# Cube_8x8x8_LED_Base.net
KiCad netlist of a schematic drawn in EAGLE
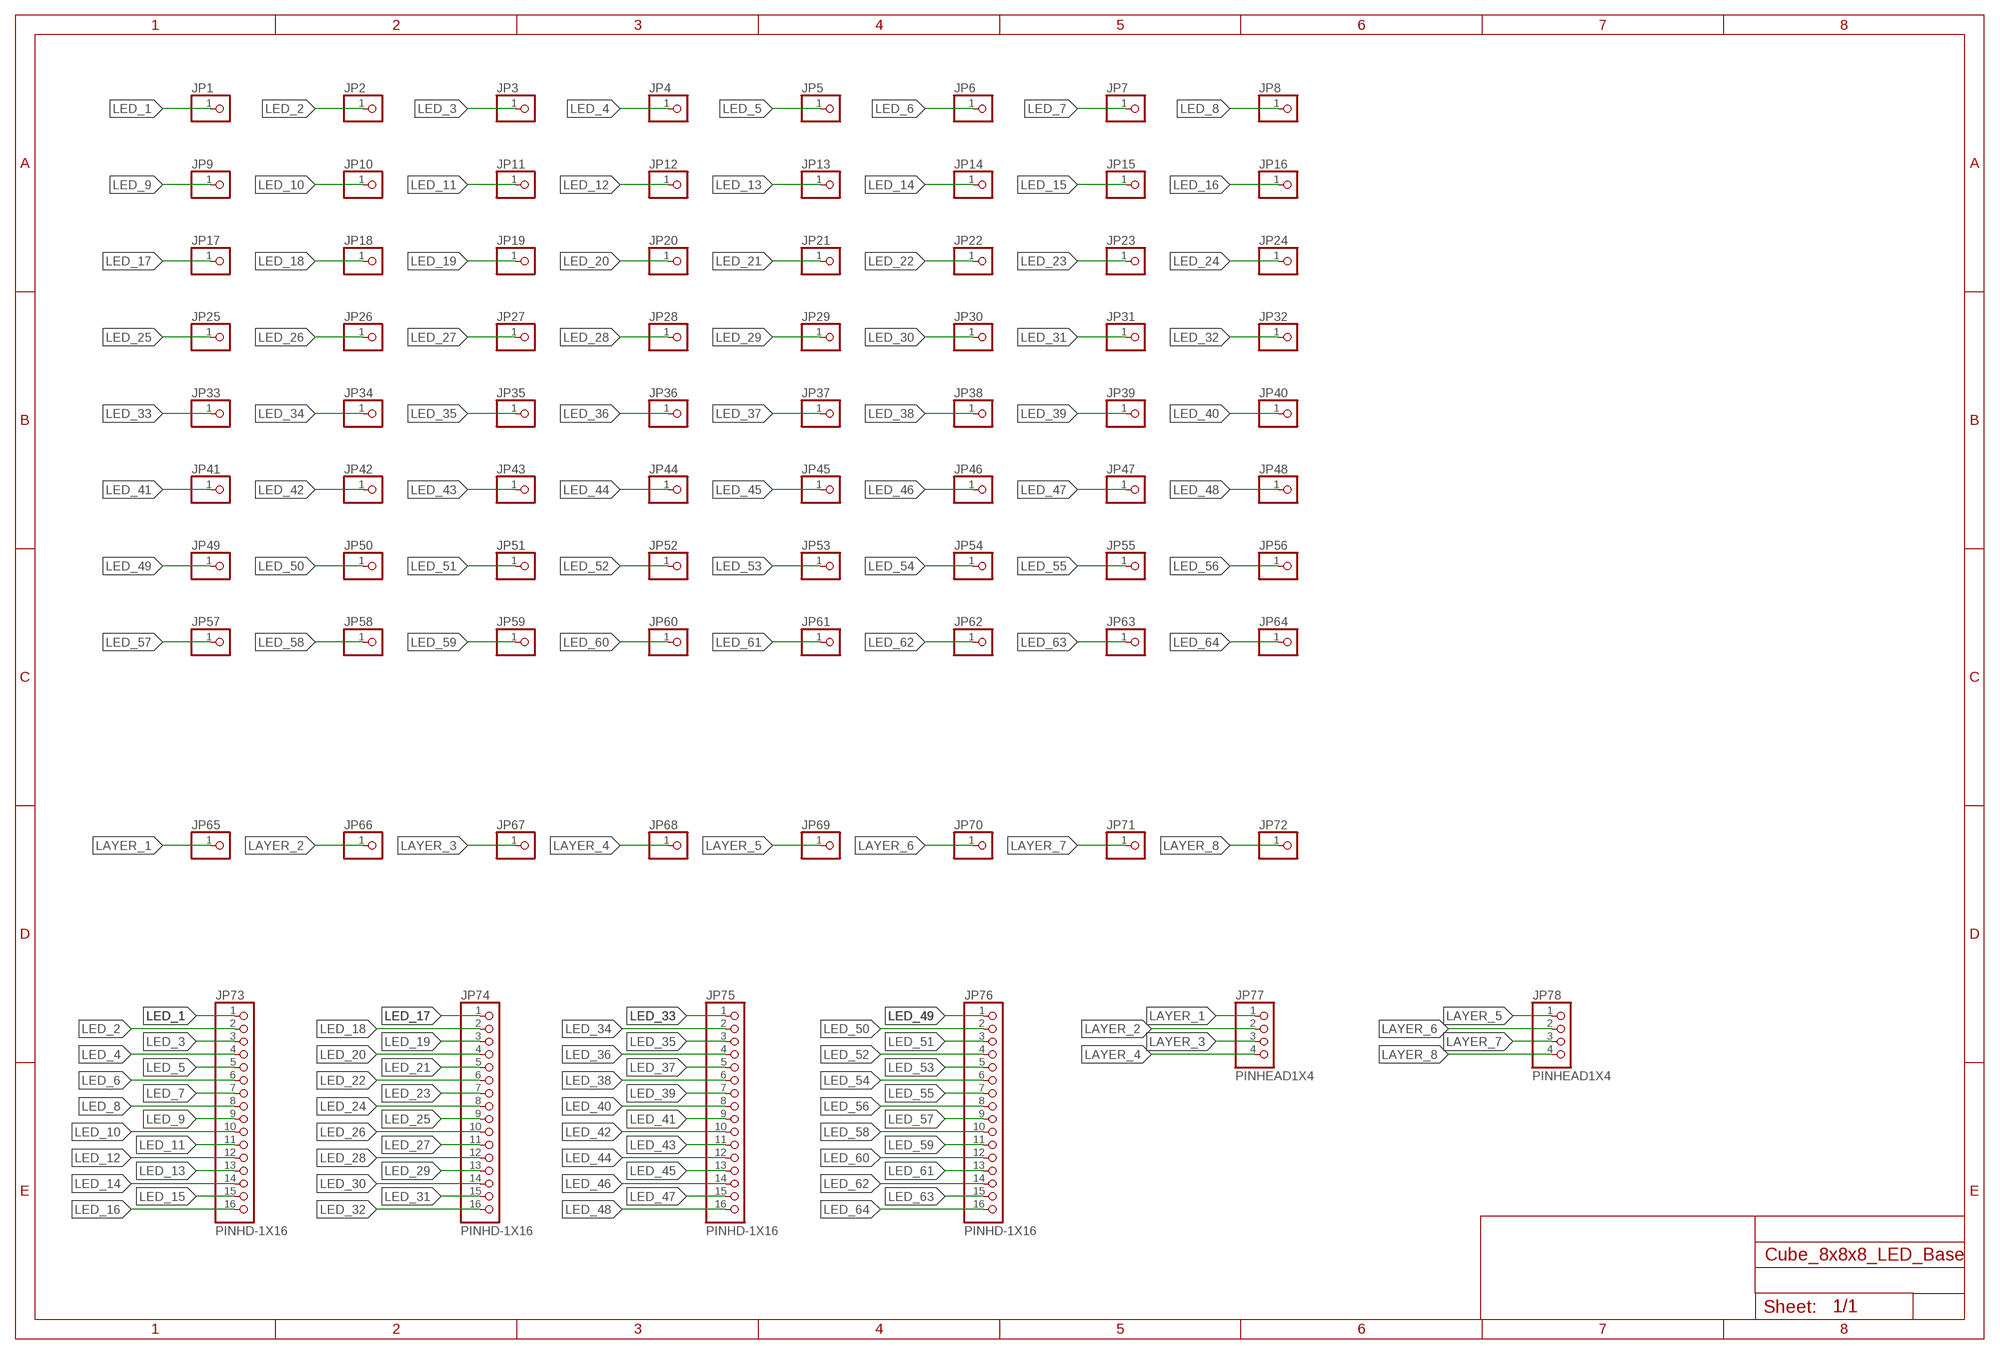
[diagram p0: schematic, sheet 1]

(export (version "E")
  (design (tool "Eeschema 10.0.6"))
  (components
    (comp (ref "JP1")
      (value "PINHD-1X1")
      (footprint "eagle-import:1X01")
      (libsource (lib "eagle-import") (part "PINHD-1X1"))
    )
    (comp (ref "JP2")
      (value "PINHD-1X1")
      (footprint "eagle-import:1X01")
      (libsource (lib "eagle-import") (part "PINHD-1X1"))
    )
    (comp (ref "JP3")
      (value "PINHD-1X1")
      (footprint "eagle-import:1X01")
      (libsource (lib "eagle-import") (part "PINHD-1X1"))
    )
    (comp (ref "JP4")
      (value "PINHD-1X1")
      (footprint "eagle-import:1X01")
      (libsource (lib "eagle-import") (part "PINHD-1X1"))
    )
    (comp (ref "JP5")
      (value "PINHD-1X1")
      (footprint "eagle-import:1X01")
      (libsource (lib "eagle-import") (part "PINHD-1X1"))
    )
    (comp (ref "JP6")
      (value "PINHD-1X1")
      (footprint "eagle-import:1X01")
      (libsource (lib "eagle-import") (part "PINHD-1X1"))
    )
    (comp (ref "JP7")
      (value "PINHD-1X1")
      (footprint "eagle-import:1X01")
      (libsource (lib "eagle-import") (part "PINHD-1X1"))
    )
    (comp (ref "JP8")
      (value "PINHD-1X1")
      (footprint "eagle-import:1X01")
      (libsource (lib "eagle-import") (part "PINHD-1X1"))
    )
    (comp (ref "JP9")
      (value "PINHD-1X1")
      (footprint "eagle-import:1X01")
      (libsource (lib "eagle-import") (part "PINHD-1X1"))
    )
    (comp (ref "JP10")
      (value "PINHD-1X1")
      (footprint "eagle-import:1X01")
      (libsource (lib "eagle-import") (part "PINHD-1X1"))
    )
    (comp (ref "JP11")
      (value "PINHD-1X1")
      (footprint "eagle-import:1X01")
      (libsource (lib "eagle-import") (part "PINHD-1X1"))
    )
    (comp (ref "JP12")
      (value "PINHD-1X1")
      (footprint "eagle-import:1X01")
      (libsource (lib "eagle-import") (part "PINHD-1X1"))
    )
    (comp (ref "JP13")
      (value "PINHD-1X1")
      (footprint "eagle-import:1X01")
      (libsource (lib "eagle-import") (part "PINHD-1X1"))
    )
    (comp (ref "JP14")
      (value "PINHD-1X1")
      (footprint "eagle-import:1X01")
      (libsource (lib "eagle-import") (part "PINHD-1X1"))
    )
    (comp (ref "JP15")
      (value "PINHD-1X1")
      (footprint "eagle-import:1X01")
      (libsource (lib "eagle-import") (part "PINHD-1X1"))
    )
    (comp (ref "JP16")
      (value "PINHD-1X1")
      (footprint "eagle-import:1X01")
      (libsource (lib "eagle-import") (part "PINHD-1X1"))
    )
    (comp (ref "JP17")
      (value "PINHD-1X1")
      (footprint "eagle-import:1X01")
      (libsource (lib "eagle-import") (part "PINHD-1X1"))
    )
    (comp (ref "JP18")
      (value "PINHD-1X1")
      (footprint "eagle-import:1X01")
      (libsource (lib "eagle-import") (part "PINHD-1X1"))
    )
    (comp (ref "JP19")
      (value "PINHD-1X1")
      (footprint "eagle-import:1X01")
      (libsource (lib "eagle-import") (part "PINHD-1X1"))
    )
    (comp (ref "JP20")
      (value "PINHD-1X1")
      (footprint "eagle-import:1X01")
      (libsource (lib "eagle-import") (part "PINHD-1X1"))
    )
    (comp (ref "JP21")
      (value "PINHD-1X1")
      (footprint "eagle-import:1X01")
      (libsource (lib "eagle-import") (part "PINHD-1X1"))
    )
    (comp (ref "JP22")
      (value "PINHD-1X1")
      (footprint "eagle-import:1X01")
      (libsource (lib "eagle-import") (part "PINHD-1X1"))
    )
    (comp (ref "JP23")
      (value "PINHD-1X1")
      (footprint "eagle-import:1X01")
      (libsource (lib "eagle-import") (part "PINHD-1X1"))
    )
    (comp (ref "JP24")
      (value "PINHD-1X1")
      (footprint "eagle-import:1X01")
      (libsource (lib "eagle-import") (part "PINHD-1X1"))
    )
    (comp (ref "JP25")
      (value "PINHD-1X1")
      (footprint "eagle-import:1X01")
      (libsource (lib "eagle-import") (part "PINHD-1X1"))
    )
    (comp (ref "JP26")
      (value "PINHD-1X1")
      (footprint "eagle-import:1X01")
      (libsource (lib "eagle-import") (part "PINHD-1X1"))
    )
    (comp (ref "JP27")
      (value "PINHD-1X1")
      (footprint "eagle-import:1X01")
      (libsource (lib "eagle-import") (part "PINHD-1X1"))
    )
    (comp (ref "JP28")
      (value "PINHD-1X1")
      (footprint "eagle-import:1X01")
      (libsource (lib "eagle-import") (part "PINHD-1X1"))
    )
    (comp (ref "JP29")
      (value "PINHD-1X1")
      (footprint "eagle-import:1X01")
      (libsource (lib "eagle-import") (part "PINHD-1X1"))
    )
    (comp (ref "JP30")
      (value "PINHD-1X1")
      (footprint "eagle-import:1X01")
      (libsource (lib "eagle-import") (part "PINHD-1X1"))
    )
    (comp (ref "JP31")
      (value "PINHD-1X1")
      (footprint "eagle-import:1X01")
      (libsource (lib "eagle-import") (part "PINHD-1X1"))
    )
    (comp (ref "JP32")
      (value "PINHD-1X1")
      (footprint "eagle-import:1X01")
      (libsource (lib "eagle-import") (part "PINHD-1X1"))
    )
    (comp (ref "JP33")
      (value "PINHD-1X1")
      (footprint "eagle-import:1X01")
      (libsource (lib "eagle-import") (part "PINHD-1X1"))
    )
    (comp (ref "JP34")
      (value "PINHD-1X1")
      (footprint "eagle-import:1X01")
      (libsource (lib "eagle-import") (part "PINHD-1X1"))
    )
    (comp (ref "JP35")
      (value "PINHD-1X1")
      (footprint "eagle-import:1X01")
      (libsource (lib "eagle-import") (part "PINHD-1X1"))
    )
    (comp (ref "JP36")
      (value "PINHD-1X1")
      (footprint "eagle-import:1X01")
      (libsource (lib "eagle-import") (part "PINHD-1X1"))
    )
    (comp (ref "JP37")
      (value "PINHD-1X1")
      (footprint "eagle-import:1X01")
      (libsource (lib "eagle-import") (part "PINHD-1X1"))
    )
    (comp (ref "JP38")
      (value "PINHD-1X1")
      (footprint "eagle-import:1X01")
      (libsource (lib "eagle-import") (part "PINHD-1X1"))
    )
    (comp (ref "JP39")
      (value "PINHD-1X1")
      (footprint "eagle-import:1X01")
      (libsource (lib "eagle-import") (part "PINHD-1X1"))
    )
    (comp (ref "JP40")
      (value "PINHD-1X1")
      (footprint "eagle-import:1X01")
      (libsource (lib "eagle-import") (part "PINHD-1X1"))
    )
    (comp (ref "JP41")
      (value "PINHD-1X1")
      (footprint "eagle-import:1X01")
      (libsource (lib "eagle-import") (part "PINHD-1X1"))
    )
    (comp (ref "JP42")
      (value "PINHD-1X1")
      (footprint "eagle-import:1X01")
      (libsource (lib "eagle-import") (part "PINHD-1X1"))
    )
    (comp (ref "JP43")
      (value "PINHD-1X1")
      (footprint "eagle-import:1X01")
      (libsource (lib "eagle-import") (part "PINHD-1X1"))
    )
    (comp (ref "JP44")
      (value "PINHD-1X1")
      (footprint "eagle-import:1X01")
      (libsource (lib "eagle-import") (part "PINHD-1X1"))
    )
    (comp (ref "JP45")
      (value "PINHD-1X1")
      (footprint "eagle-import:1X01")
      (libsource (lib "eagle-import") (part "PINHD-1X1"))
    )
    (comp (ref "JP46")
      (value "PINHD-1X1")
      (footprint "eagle-import:1X01")
      (libsource (lib "eagle-import") (part "PINHD-1X1"))
    )
    (comp (ref "JP47")
      (value "PINHD-1X1")
      (footprint "eagle-import:1X01")
      (libsource (lib "eagle-import") (part "PINHD-1X1"))
    )
    (comp (ref "JP48")
      (value "PINHD-1X1")
      (footprint "eagle-import:1X01")
      (libsource (lib "eagle-import") (part "PINHD-1X1"))
    )
    (comp (ref "JP49")
      (value "PINHD-1X1")
      (footprint "eagle-import:1X01")
      (libsource (lib "eagle-import") (part "PINHD-1X1"))
    )
    (comp (ref "JP50")
      (value "PINHD-1X1")
      (footprint "eagle-import:1X01")
      (libsource (lib "eagle-import") (part "PINHD-1X1"))
    )
    (comp (ref "JP51")
      (value "PINHD-1X1")
      (footprint "eagle-import:1X01")
      (libsource (lib "eagle-import") (part "PINHD-1X1"))
    )
    (comp (ref "JP52")
      (value "PINHD-1X1")
      (footprint "eagle-import:1X01")
      (libsource (lib "eagle-import") (part "PINHD-1X1"))
    )
    (comp (ref "JP53")
      (value "PINHD-1X1")
      (footprint "eagle-import:1X01")
      (libsource (lib "eagle-import") (part "PINHD-1X1"))
    )
    (comp (ref "JP54")
      (value "PINHD-1X1")
      (footprint "eagle-import:1X01")
      (libsource (lib "eagle-import") (part "PINHD-1X1"))
    )
    (comp (ref "JP55")
      (value "PINHD-1X1")
      (footprint "eagle-import:1X01")
      (libsource (lib "eagle-import") (part "PINHD-1X1"))
    )
    (comp (ref "JP56")
      (value "PINHD-1X1")
      (footprint "eagle-import:1X01")
      (libsource (lib "eagle-import") (part "PINHD-1X1"))
    )
    (comp (ref "JP57")
      (value "PINHD-1X1")
      (footprint "eagle-import:1X01")
      (libsource (lib "eagle-import") (part "PINHD-1X1"))
    )
    (comp (ref "JP58")
      (value "PINHD-1X1")
      (footprint "eagle-import:1X01")
      (libsource (lib "eagle-import") (part "PINHD-1X1"))
    )
    (comp (ref "JP59")
      (value "PINHD-1X1")
      (footprint "eagle-import:1X01")
      (libsource (lib "eagle-import") (part "PINHD-1X1"))
    )
    (comp (ref "JP60")
      (value "PINHD-1X1")
      (footprint "eagle-import:1X01")
      (libsource (lib "eagle-import") (part "PINHD-1X1"))
    )
    (comp (ref "JP61")
      (value "PINHD-1X1")
      (footprint "eagle-import:1X01")
      (libsource (lib "eagle-import") (part "PINHD-1X1"))
    )
    (comp (ref "JP62")
      (value "PINHD-1X1")
      (footprint "eagle-import:1X01")
      (libsource (lib "eagle-import") (part "PINHD-1X1"))
    )
    (comp (ref "JP63")
      (value "PINHD-1X1")
      (footprint "eagle-import:1X01")
      (libsource (lib "eagle-import") (part "PINHD-1X1"))
    )
    (comp (ref "JP64")
      (value "PINHD-1X1")
      (footprint "eagle-import:1X01")
      (libsource (lib "eagle-import") (part "PINHD-1X1"))
    )
    (comp (ref "JP65")
      (value "PINHD-1X1")
      (footprint "eagle-import:1X01")
      (libsource (lib "eagle-import") (part "PINHD-1X1"))
    )
    (comp (ref "JP66")
      (value "PINHD-1X1")
      (footprint "eagle-import:1X01")
      (libsource (lib "eagle-import") (part "PINHD-1X1"))
    )
    (comp (ref "JP67")
      (value "PINHD-1X1")
      (footprint "eagle-import:1X01")
      (libsource (lib "eagle-import") (part "PINHD-1X1"))
    )
    (comp (ref "JP68")
      (value "PINHD-1X1")
      (footprint "eagle-import:1X01")
      (libsource (lib "eagle-import") (part "PINHD-1X1"))
    )
    (comp (ref "JP69")
      (value "PINHD-1X1")
      (footprint "eagle-import:1X01")
      (libsource (lib "eagle-import") (part "PINHD-1X1"))
    )
    (comp (ref "JP70")
      (value "PINHD-1X1")
      (footprint "eagle-import:1X01")
      (libsource (lib "eagle-import") (part "PINHD-1X1"))
    )
    (comp (ref "JP71")
      (value "PINHD-1X1")
      (footprint "eagle-import:1X01")
      (libsource (lib "eagle-import") (part "PINHD-1X1"))
    )
    (comp (ref "JP72")
      (value "PINHD-1X1")
      (footprint "eagle-import:1X01")
      (libsource (lib "eagle-import") (part "PINHD-1X1"))
    )
    (comp (ref "JP73")
      (value "PINHD-1X16")
      (footprint "eagle-import:2X16")
      (libsource (lib "eagle-import") (part "PINHD-1X16"))
    )
    (comp (ref "JP74")
      (value "PINHD-1X16")
      (footprint "eagle-import:2X16")
      (libsource (lib "eagle-import") (part "PINHD-1X16"))
    )
    (comp (ref "JP75")
      (value "PINHD-1X16")
      (footprint "eagle-import:2X16")
      (libsource (lib "eagle-import") (part "PINHD-1X16"))
    )
    (comp (ref "JP76")
      (value "PINHD-1X16")
      (footprint "eagle-import:2X16")
      (libsource (lib "eagle-import") (part "PINHD-1X16"))
    )
    (comp (ref "JP77")
      (value "PINHEAD1X4")
      (footprint "eagle-import:2X04")
      (libsource (lib "eagle-import") (part "PINHEAD1X4"))
    )
    (comp (ref "JP78")
      (value "PINHEAD1X4")
      (footprint "eagle-import:2X04")
      (libsource (lib "eagle-import") (part "PINHEAD1X4"))
    )
  )
  (nets
    (net (code "1") (name "LAYER_1") (class "Default")
      (node (ref "JP65") (pin "1") (pinfunction "1_1") (pintype "passive"))
      (node (ref "JP77") (pin "1") (pinfunction "1_1") (pintype "passive"))
    )
    (net (code "2") (name "LAYER_2") (class "Default")
      (node (ref "JP66") (pin "1") (pinfunction "1_1") (pintype "passive"))
      (node (ref "JP77") (pin "2") (pinfunction "2_2") (pintype "passive"))
    )
    (net (code "3") (name "LAYER_3") (class "Default")
      (node (ref "JP67") (pin "1") (pinfunction "1_1") (pintype "passive"))
      (node (ref "JP77") (pin "3") (pinfunction "3_3") (pintype "passive"))
    )
    (net (code "4") (name "LAYER_4") (class "Default")
      (node (ref "JP68") (pin "1") (pinfunction "1_1") (pintype "passive"))
      (node (ref "JP77") (pin "4") (pinfunction "4_4") (pintype "passive"))
    )
    (net (code "5") (name "LAYER_5") (class "Default")
      (node (ref "JP69") (pin "1") (pinfunction "1_1") (pintype "passive"))
      (node (ref "JP78") (pin "1") (pinfunction "1_1") (pintype "passive"))
    )
    (net (code "6") (name "LAYER_6") (class "Default")
      (node (ref "JP70") (pin "1") (pinfunction "1_1") (pintype "passive"))
      (node (ref "JP78") (pin "2") (pinfunction "2_2") (pintype "passive"))
    )
    (net (code "7") (name "LAYER_7") (class "Default")
      (node (ref "JP71") (pin "1") (pinfunction "1_1") (pintype "passive"))
      (node (ref "JP78") (pin "3") (pinfunction "3_3") (pintype "passive"))
    )
    (net (code "8") (name "LAYER_8") (class "Default")
      (node (ref "JP72") (pin "1") (pinfunction "1_1") (pintype "passive"))
      (node (ref "JP78") (pin "4") (pinfunction "4_4") (pintype "passive"))
    )
    (net (code "9") (name "LED_1") (class "Default")
      (node (ref "JP1") (pin "1") (pinfunction "1_1") (pintype "passive"))
      (node (ref "JP73") (pin "1") (pinfunction "1_1") (pintype "passive"))
    )
    (net (code "10") (name "LED_2") (class "Default")
      (node (ref "JP2") (pin "1") (pinfunction "1_1") (pintype "passive"))
      (node (ref "JP73") (pin "2") (pinfunction "2_2") (pintype "passive"))
    )
    (net (code "11") (name "LED_3") (class "Default")
      (node (ref "JP3") (pin "1") (pinfunction "1_1") (pintype "passive"))
      (node (ref "JP73") (pin "3") (pinfunction "3_3") (pintype "passive"))
    )
    (net (code "12") (name "LED_4") (class "Default")
      (node (ref "JP4") (pin "1") (pinfunction "1_1") (pintype "passive"))
      (node (ref "JP73") (pin "4") (pinfunction "4_4") (pintype "passive"))
    )
    (net (code "13") (name "LED_5") (class "Default")
      (node (ref "JP5") (pin "1") (pinfunction "1_1") (pintype "passive"))
      (node (ref "JP73") (pin "5") (pinfunction "5_5") (pintype "passive"))
    )
    (net (code "14") (name "LED_6") (class "Default")
      (node (ref "JP6") (pin "1") (pinfunction "1_1") (pintype "passive"))
      (node (ref "JP73") (pin "6") (pinfunction "6_6") (pintype "passive"))
    )
    (net (code "15") (name "LED_7") (class "Default")
      (node (ref "JP7") (pin "1") (pinfunction "1_1") (pintype "passive"))
      (node (ref "JP73") (pin "7") (pinfunction "7_7") (pintype "passive"))
    )
    (net (code "16") (name "LED_8") (class "Default")
      (node (ref "JP73") (pin "8") (pinfunction "8_8") (pintype "passive"))
      (node (ref "JP8") (pin "1") (pinfunction "1_1") (pintype "passive"))
    )
    (net (code "17") (name "LED_9") (class "Default")
      (node (ref "JP73") (pin "9") (pinfunction "9_9") (pintype "passive"))
      (node (ref "JP9") (pin "1") (pinfunction "1_1") (pintype "passive"))
    )
    (net (code "18") (name "LED_10") (class "Default")
      (node (ref "JP10") (pin "1") (pinfunction "1_1") (pintype "passive"))
      (node (ref "JP73") (pin "10") (pinfunction "10_10") (pintype "passive"))
    )
    (net (code "19") (name "LED_11") (class "Default")
      (node (ref "JP11") (pin "1") (pinfunction "1_1") (pintype "passive"))
      (node (ref "JP73") (pin "11") (pinfunction "11_11") (pintype "passive"))
    )
    (net (code "20") (name "LED_12") (class "Default")
      (node (ref "JP12") (pin "1") (pinfunction "1_1") (pintype "passive"))
      (node (ref "JP73") (pin "12") (pinfunction "12_12") (pintype "passive"))
    )
    (net (code "21") (name "LED_13") (class "Default")
      (node (ref "JP13") (pin "1") (pinfunction "1_1") (pintype "passive"))
      (node (ref "JP73") (pin "13") (pinfunction "13_13") (pintype "passive"))
    )
    (net (code "22") (name "LED_14") (class "Default")
      (node (ref "JP14") (pin "1") (pinfunction "1_1") (pintype "passive"))
      (node (ref "JP73") (pin "14") (pinfunction "14_14") (pintype "passive"))
    )
    (net (code "23") (name "LED_15") (class "Default")
      (node (ref "JP15") (pin "1") (pinfunction "1_1") (pintype "passive"))
      (node (ref "JP73") (pin "15") (pinfunction "15_15") (pintype "passive"))
    )
    (net (code "24") (name "LED_16") (class "Default")
      (node (ref "JP16") (pin "1") (pinfunction "1_1") (pintype "passive"))
      (node (ref "JP73") (pin "16") (pinfunction "16_16") (pintype "passive"))
    )
    (net (code "25") (name "LED_17") (class "Default")
      (node (ref "JP17") (pin "1") (pinfunction "1_1") (pintype "passive"))
      (node (ref "JP74") (pin "1") (pinfunction "1_1") (pintype "passive"))
    )
    (net (code "26") (name "LED_18") (class "Default")
      (node (ref "JP18") (pin "1") (pinfunction "1_1") (pintype "passive"))
      (node (ref "JP74") (pin "2") (pinfunction "2_2") (pintype "passive"))
    )
    (net (code "27") (name "LED_19") (class "Default")
      (node (ref "JP19") (pin "1") (pinfunction "1_1") (pintype "passive"))
      (node (ref "JP74") (pin "3") (pinfunction "3_3") (pintype "passive"))
    )
    (net (code "28") (name "LED_20") (class "Default")
      (node (ref "JP20") (pin "1") (pinfunction "1_1") (pintype "passive"))
      (node (ref "JP74") (pin "4") (pinfunction "4_4") (pintype "passive"))
    )
    (net (code "29") (name "LED_21") (class "Default")
      (node (ref "JP21") (pin "1") (pinfunction "1_1") (pintype "passive"))
      (node (ref "JP74") (pin "5") (pinfunction "5_5") (pintype "passive"))
    )
    (net (code "30") (name "LED_22") (class "Default")
      (node (ref "JP22") (pin "1") (pinfunction "1_1") (pintype "passive"))
      (node (ref "JP74") (pin "6") (pinfunction "6_6") (pintype "passive"))
    )
    (net (code "31") (name "LED_23") (class "Default")
      (node (ref "JP23") (pin "1") (pinfunction "1_1") (pintype "passive"))
      (node (ref "JP74") (pin "7") (pinfunction "7_7") (pintype "passive"))
    )
    (net (code "32") (name "LED_24") (class "Default")
      (node (ref "JP24") (pin "1") (pinfunction "1_1") (pintype "passive"))
      (node (ref "JP74") (pin "8") (pinfunction "8_8") (pintype "passive"))
    )
    (net (code "33") (name "LED_25") (class "Default")
      (node (ref "JP25") (pin "1") (pinfunction "1_1") (pintype "passive"))
      (node (ref "JP74") (pin "9") (pinfunction "9_9") (pintype "passive"))
    )
    (net (code "34") (name "LED_26") (class "Default")
      (node (ref "JP26") (pin "1") (pinfunction "1_1") (pintype "passive"))
      (node (ref "JP74") (pin "10") (pinfunction "10_10") (pintype "passive"))
    )
    (net (code "35") (name "LED_27") (class "Default")
      (node (ref "JP27") (pin "1") (pinfunction "1_1") (pintype "passive"))
      (node (ref "JP74") (pin "11") (pinfunction "11_11") (pintype "passive"))
    )
    (net (code "36") (name "LED_28") (class "Default")
      (node (ref "JP28") (pin "1") (pinfunction "1_1") (pintype "passive"))
      (node (ref "JP74") (pin "12") (pinfunction "12_12") (pintype "passive"))
    )
    (net (code "37") (name "LED_29") (class "Default")
      (node (ref "JP29") (pin "1") (pinfunction "1_1") (pintype "passive"))
      (node (ref "JP74") (pin "13") (pinfunction "13_13") (pintype "passive"))
    )
    (net (code "38") (name "LED_30") (class "Default")
      (node (ref "JP30") (pin "1") (pinfunction "1_1") (pintype "passive"))
      (node (ref "JP74") (pin "14") (pinfunction "14_14") (pintype "passive"))
    )
    (net (code "39") (name "LED_31") (class "Default")
      (node (ref "JP31") (pin "1") (pinfunction "1_1") (pintype "passive"))
      (node (ref "JP74") (pin "15") (pinfunction "15_15") (pintype "passive"))
    )
    (net (code "40") (name "LED_32") (class "Default")
      (node (ref "JP32") (pin "1") (pinfunction "1_1") (pintype "passive"))
      (node (ref "JP74") (pin "16") (pinfunction "16_16") (pintype "passive"))
    )
    (net (code "41") (name "LED_33") (class "Default")
      (node (ref "JP33") (pin "1") (pinfunction "1_1") (pintype "passive"))
      (node (ref "JP75") (pin "1") (pinfunction "1_1") (pintype "passive"))
    )
    (net (code "42") (name "LED_34") (class "Default")
      (node (ref "JP34") (pin "1") (pinfunction "1_1") (pintype "passive"))
      (node (ref "JP75") (pin "2") (pinfunction "2_2") (pintype "passive"))
    )
    (net (code "43") (name "LED_35") (class "Default")
      (node (ref "JP35") (pin "1") (pinfunction "1_1") (pintype "passive"))
      (node (ref "JP75") (pin "3") (pinfunction "3_3") (pintype "passive"))
    )
    (net (code "44") (name "LED_36") (class "Default")
      (node (ref "JP36") (pin "1") (pinfunction "1_1") (pintype "passive"))
      (node (ref "JP75") (pin "4") (pinfunction "4_4") (pintype "passive"))
    )
    (net (code "45") (name "LED_37") (class "Default")
      (node (ref "JP37") (pin "1") (pinfunction "1_1") (pintype "passive"))
      (node (ref "JP75") (pin "5") (pinfunction "5_5") (pintype "passive"))
    )
    (net (code "46") (name "LED_38") (class "Default")
      (node (ref "JP38") (pin "1") (pinfunction "1_1") (pintype "passive"))
      (node (ref "JP75") (pin "6") (pinfunction "6_6") (pintype "passive"))
    )
    (net (code "47") (name "LED_39") (class "Default")
      (node (ref "JP39") (pin "1") (pinfunction "1_1") (pintype "passive"))
      (node (ref "JP75") (pin "7") (pinfunction "7_7") (pintype "passive"))
    )
    (net (code "48") (name "LED_40") (class "Default")
      (node (ref "JP40") (pin "1") (pinfunction "1_1") (pintype "passive"))
      (node (ref "JP75") (pin "8") (pinfunction "8_8") (pintype "passive"))
    )
    (net (code "49") (name "LED_41") (class "Default")
      (node (ref "JP41") (pin "1") (pinfunction "1_1") (pintype "passive"))
      (node (ref "JP75") (pin "9") (pinfunction "9_9") (pintype "passive"))
    )
    (net (code "50") (name "LED_42") (class "Default")
      (node (ref "JP42") (pin "1") (pinfunction "1_1") (pintype "passive"))
      (node (ref "JP75") (pin "10") (pinfunction "10_10") (pintype "passive"))
    )
    (net (code "51") (name "LED_43") (class "Default")
      (node (ref "JP43") (pin "1") (pinfunction "1_1") (pintype "passive"))
      (node (ref "JP75") (pin "11") (pinfunction "11_11") (pintype "passive"))
    )
    (net (code "52") (name "LED_44") (class "Default")
      (node (ref "JP44") (pin "1") (pinfunction "1_1") (pintype "passive"))
      (node (ref "JP75") (pin "12") (pinfunction "12_12") (pintype "passive"))
    )
    (net (code "53") (name "LED_45") (class "Default")
      (node (ref "JP45") (pin "1") (pinfunction "1_1") (pintype "passive"))
      (node (ref "JP75") (pin "13") (pinfunction "13_13") (pintype "passive"))
    )
    (net (code "54") (name "LED_46") (class "Default")
      (node (ref "JP46") (pin "1") (pinfunction "1_1") (pintype "passive"))
      (node (ref "JP75") (pin "14") (pinfunction "14_14") (pintype "passive"))
    )
    (net (code "55") (name "LED_47") (class "Default")
      (node (ref "JP47") (pin "1") (pinfunction "1_1") (pintype "passive"))
      (node (ref "JP75") (pin "15") (pinfunction "15_15") (pintype "passive"))
    )
    (net (code "56") (name "LED_48") (class "Default")
      (node (ref "JP48") (pin "1") (pinfunction "1_1") (pintype "passive"))
      (node (ref "JP75") (pin "16") (pinfunction "16_16") (pintype "passive"))
    )
    (net (code "57") (name "LED_49") (class "Default")
      (node (ref "JP49") (pin "1") (pinfunction "1_1") (pintype "passive"))
      (node (ref "JP76") (pin "1") (pinfunction "1_1") (pintype "passive"))
    )
    (net (code "58") (name "LED_50") (class "Default")
      (node (ref "JP50") (pin "1") (pinfunction "1_1") (pintype "passive"))
      (node (ref "JP76") (pin "2") (pinfunction "2_2") (pintype "passive"))
    )
    (net (code "59") (name "LED_51") (class "Default")
      (node (ref "JP51") (pin "1") (pinfunction "1_1") (pintype "passive"))
      (node (ref "JP76") (pin "3") (pinfunction "3_3") (pintype "passive"))
    )
    (net (code "60") (name "LED_52") (class "Default")
      (node (ref "JP52") (pin "1") (pinfunction "1_1") (pintype "passive"))
      (node (ref "JP76") (pin "4") (pinfunction "4_4") (pintype "passive"))
    )
    (net (code "61") (name "LED_53") (class "Default")
      (node (ref "JP53") (pin "1") (pinfunction "1_1") (pintype "passive"))
      (node (ref "JP76") (pin "5") (pinfunction "5_5") (pintype "passive"))
    )
    (net (code "62") (name "LED_54") (class "Default")
      (node (ref "JP54") (pin "1") (pinfunction "1_1") (pintype "passive"))
      (node (ref "JP76") (pin "6") (pinfunction "6_6") (pintype "passive"))
    )
    (net (code "63") (name "LED_55") (class "Default")
      (node (ref "JP55") (pin "1") (pinfunction "1_1") (pintype "passive"))
      (node (ref "JP76") (pin "7") (pinfunction "7_7") (pintype "passive"))
    )
    (net (code "64") (name "LED_56") (class "Default")
      (node (ref "JP56") (pin "1") (pinfunction "1_1") (pintype "passive"))
      (node (ref "JP76") (pin "8") (pinfunction "8_8") (pintype "passive"))
    )
    (net (code "65") (name "LED_57") (class "Default")
      (node (ref "JP57") (pin "1") (pinfunction "1_1") (pintype "passive"))
      (node (ref "JP76") (pin "9") (pinfunction "9_9") (pintype "passive"))
    )
    (net (code "66") (name "LED_58") (class "Default")
      (node (ref "JP58") (pin "1") (pinfunction "1_1") (pintype "passive"))
      (node (ref "JP76") (pin "10") (pinfunction "10_10") (pintype "passive"))
    )
    (net (code "67") (name "LED_59") (class "Default")
      (node (ref "JP59") (pin "1") (pinfunction "1_1") (pintype "passive"))
      (node (ref "JP76") (pin "11") (pinfunction "11_11") (pintype "passive"))
    )
    (net (code "68") (name "LED_60") (class "Default")
      (node (ref "JP60") (pin "1") (pinfunction "1_1") (pintype "passive"))
      (node (ref "JP76") (pin "12") (pinfunction "12_12") (pintype "passive"))
    )
    (net (code "69") (name "LED_61") (class "Default")
      (node (ref "JP61") (pin "1") (pinfunction "1_1") (pintype "passive"))
      (node (ref "JP76") (pin "13") (pinfunction "13_13") (pintype "passive"))
    )
    (net (code "70") (name "LED_62") (class "Default")
      (node (ref "JP62") (pin "1") (pinfunction "1_1") (pintype "passive"))
      (node (ref "JP76") (pin "14") (pinfunction "14_14") (pintype "passive"))
    )
    (net (code "71") (name "LED_63") (class "Default")
      (node (ref "JP63") (pin "1") (pinfunction "1_1") (pintype "passive"))
      (node (ref "JP76") (pin "15") (pinfunction "15_15") (pintype "passive"))
    )
    (net (code "72") (name "LED_64") (class "Default")
      (node (ref "JP64") (pin "1") (pinfunction "1_1") (pintype "passive"))
      (node (ref "JP76") (pin "16") (pinfunction "16_16") (pintype "passive"))
    )
  )
)
